# core_power.net
KiCad netlist of a schematic drawn in Altium Designer
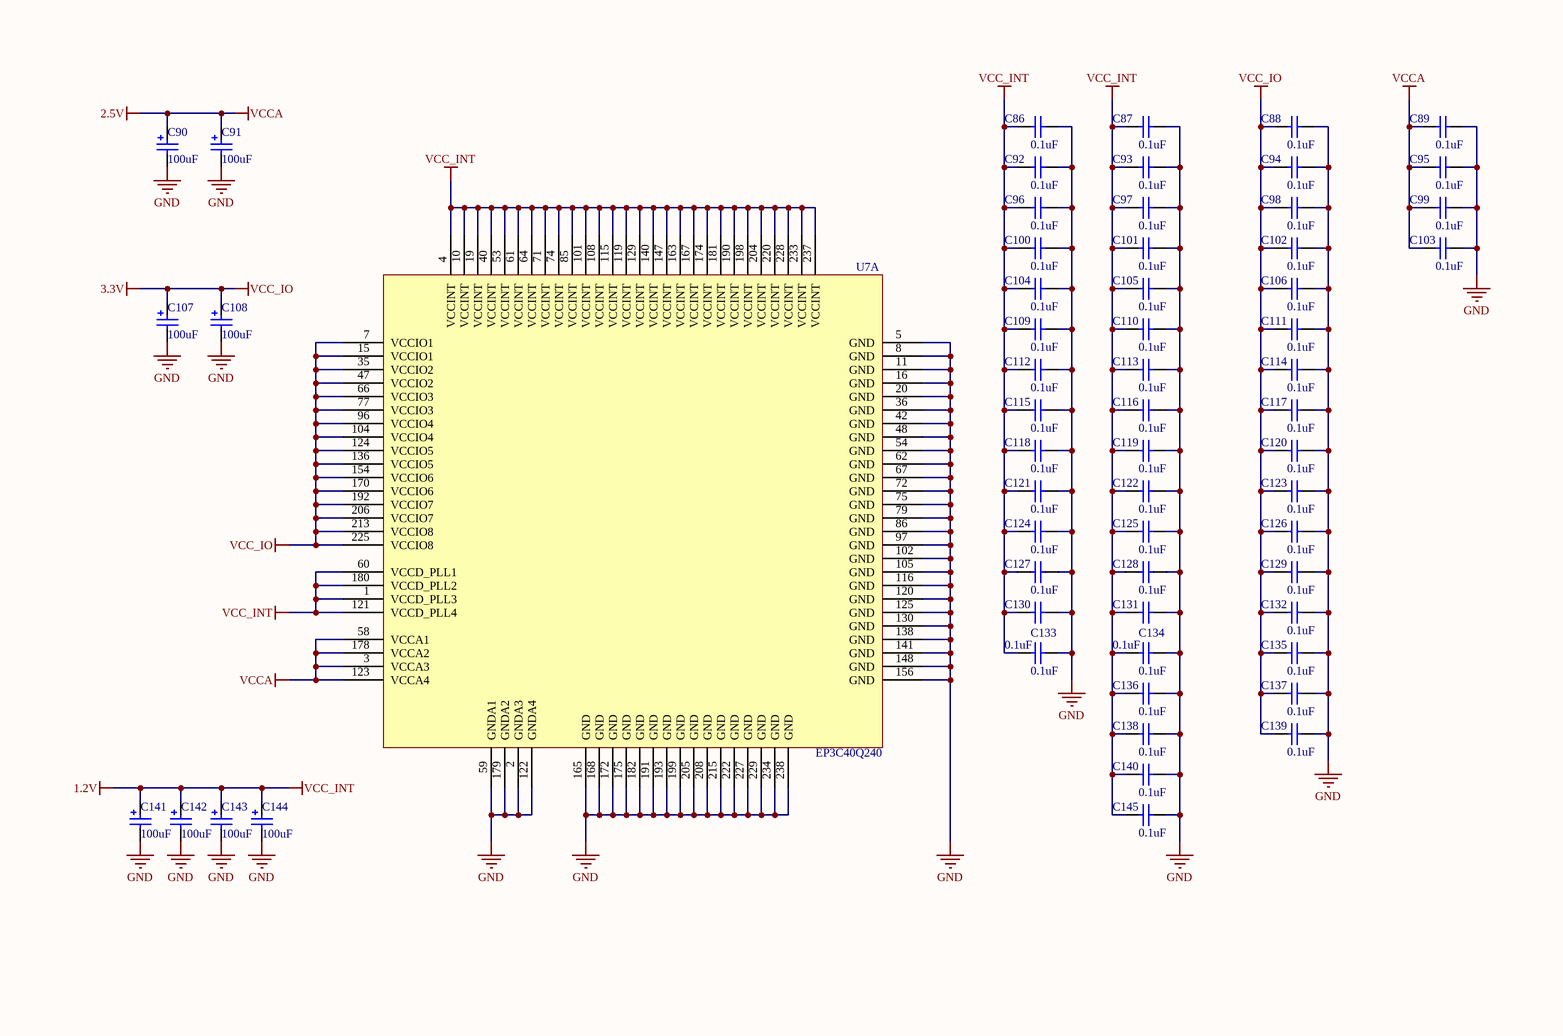
[diagram p0: core_power.SchDoc]

(export (version "E")
  (design (tool "Eeschema 10.0.6"))
  (components
    (comp (ref "C86")
      (value "0.1uF")
      (footprint "0402")
      (description "Capacitor")
      (fields (field (name "Comment") "Cap") (field (name "PUBLISHER") "Altium Limited"))
      (libsource (lib "Miscellaneous Devices") (part "Cap"))
    )
    (comp (ref "C87")
      (value "0.1uF")
      (footprint "0402")
      (description "Capacitor")
      (fields (field (name "Comment") "Cap") (field (name "PUBLISHER") "Altium Limited"))
      (libsource (lib "Miscellaneous Devices") (part "Cap"))
    )
    (comp (ref "C88")
      (value "0.1uF")
      (footprint "0402")
      (description "Capacitor")
      (fields (field (name "Comment") "Cap") (field (name "PUBLISHER") "Altium Limited"))
      (libsource (lib "Miscellaneous Devices") (part "Cap"))
    )
    (comp (ref "C89")
      (value "0.1uF")
      (footprint "0402")
      (description "Capacitor")
      (fields (field (name "Comment") "Cap") (field (name "PUBLISHER") "Altium Limited"))
      (libsource (lib "Miscellaneous Devices") (part "Cap"))
    )
    (comp (ref "C90")
      (value "100uF")
      (footprint "C1206_POLARIZED")
      (description "Polarized Capacitor (Axial)")
      (fields (field (name "Comment") "Cap") (field (name "PUBLISHER") "Altium Limited"))
      (libsource (lib "Miscellaneous Devices") (part "Cap Pol2"))
    )
    (comp (ref "C91")
      (value "100uF")
      (footprint "C1206_POLARIZED")
      (description "Polarized Capacitor (Axial)")
      (fields (field (name "Comment") "Cap") (field (name "PUBLISHER") "Altium Limited"))
      (libsource (lib "Miscellaneous Devices") (part "Cap Pol2"))
    )
    (comp (ref "C92")
      (value "0.1uF")
      (footprint "0402")
      (description "Capacitor")
      (fields (field (name "Comment") "Cap") (field (name "PUBLISHER") "Altium Limited"))
      (libsource (lib "Miscellaneous Devices") (part "Cap"))
    )
    (comp (ref "C93")
      (value "0.1uF")
      (footprint "0402")
      (description "Capacitor")
      (fields (field (name "Comment") "Cap") (field (name "PUBLISHER") "Altium Limited"))
      (libsource (lib "Miscellaneous Devices") (part "Cap"))
    )
    (comp (ref "C94")
      (value "0.1uF")
      (footprint "0402")
      (description "Capacitor")
      (fields (field (name "Comment") "Cap") (field (name "PUBLISHER") "Altium Limited"))
      (libsource (lib "Miscellaneous Devices") (part "Cap"))
    )
    (comp (ref "C95")
      (value "0.1uF")
      (footprint "0402")
      (description "Capacitor")
      (fields (field (name "Comment") "Cap") (field (name "PUBLISHER") "Altium Limited"))
      (libsource (lib "Miscellaneous Devices") (part "Cap"))
    )
    (comp (ref "C96")
      (value "0.1uF")
      (footprint "0402")
      (description "Capacitor")
      (fields (field (name "Comment") "Cap") (field (name "PUBLISHER") "Altium Limited"))
      (libsource (lib "Miscellaneous Devices") (part "Cap"))
    )
    (comp (ref "C97")
      (value "0.1uF")
      (footprint "0402")
      (description "Capacitor")
      (fields (field (name "Comment") "Cap") (field (name "PUBLISHER") "Altium Limited"))
      (libsource (lib "Miscellaneous Devices") (part "Cap"))
    )
    (comp (ref "C98")
      (value "0.1uF")
      (footprint "0402")
      (description "Capacitor")
      (fields (field (name "Comment") "Cap") (field (name "PUBLISHER") "Altium Limited"))
      (libsource (lib "Miscellaneous Devices") (part "Cap"))
    )
    (comp (ref "C99")
      (value "0.1uF")
      (footprint "0402")
      (description "Capacitor")
      (fields (field (name "Comment") "Cap") (field (name "PUBLISHER") "Altium Limited"))
      (libsource (lib "Miscellaneous Devices") (part "Cap"))
    )
    (comp (ref "C100")
      (value "0.1uF")
      (footprint "0402")
      (description "Capacitor")
      (fields (field (name "Comment") "Cap") (field (name "PUBLISHER") "Altium Limited"))
      (libsource (lib "Miscellaneous Devices") (part "Cap"))
    )
    (comp (ref "C101")
      (value "0.1uF")
      (footprint "0402")
      (description "Capacitor")
      (fields (field (name "Comment") "Cap") (field (name "PUBLISHER") "Altium Limited"))
      (libsource (lib "Miscellaneous Devices") (part "Cap"))
    )
    (comp (ref "C102")
      (value "0.1uF")
      (footprint "0402")
      (description "Capacitor")
      (fields (field (name "Comment") "Cap") (field (name "PUBLISHER") "Altium Limited"))
      (libsource (lib "Miscellaneous Devices") (part "Cap"))
    )
    (comp (ref "C103")
      (value "0.1uF")
      (footprint "0402")
      (description "Capacitor")
      (fields (field (name "Comment") "Cap") (field (name "PUBLISHER") "Altium Limited"))
      (libsource (lib "Miscellaneous Devices") (part "Cap"))
    )
    (comp (ref "C104")
      (value "0.1uF")
      (footprint "0402")
      (description "Capacitor")
      (fields (field (name "Comment") "Cap") (field (name "PUBLISHER") "Altium Limited"))
      (libsource (lib "Miscellaneous Devices") (part "Cap"))
    )
    (comp (ref "C105")
      (value "0.1uF")
      (footprint "0402")
      (description "Capacitor")
      (fields (field (name "Comment") "Cap") (field (name "PUBLISHER") "Altium Limited"))
      (libsource (lib "Miscellaneous Devices") (part "Cap"))
    )
    (comp (ref "C106")
      (value "0.1uF")
      (footprint "0402")
      (description "Capacitor")
      (fields (field (name "Comment") "Cap") (field (name "PUBLISHER") "Altium Limited"))
      (libsource (lib "Miscellaneous Devices") (part "Cap"))
    )
    (comp (ref "C107")
      (value "100uF")
      (footprint "C1206_POLARIZED")
      (description "Polarized Capacitor (Axial)")
      (fields (field (name "Comment") "Cap") (field (name "PUBLISHER") "Altium Limited"))
      (libsource (lib "Miscellaneous Devices") (part "Cap Pol2"))
    )
    (comp (ref "C108")
      (value "100uF")
      (footprint "C1206_POLARIZED")
      (description "Polarized Capacitor (Axial)")
      (fields (field (name "Comment") "Cap") (field (name "PUBLISHER") "Altium Limited"))
      (libsource (lib "Miscellaneous Devices") (part "Cap Pol2"))
    )
    (comp (ref "C109")
      (value "0.1uF")
      (footprint "0402")
      (description "Capacitor")
      (fields (field (name "Comment") "Cap") (field (name "PUBLISHER") "Altium Limited"))
      (libsource (lib "Miscellaneous Devices") (part "Cap"))
    )
    (comp (ref "C110")
      (value "0.1uF")
      (footprint "0402")
      (description "Capacitor")
      (fields (field (name "Comment") "Cap") (field (name "PUBLISHER") "Altium Limited"))
      (libsource (lib "Miscellaneous Devices") (part "Cap"))
    )
    (comp (ref "C111")
      (value "0.1uF")
      (footprint "0402")
      (description "Capacitor")
      (fields (field (name "Comment") "Cap") (field (name "PUBLISHER") "Altium Limited"))
      (libsource (lib "Miscellaneous Devices") (part "Cap"))
    )
    (comp (ref "C112")
      (value "0.1uF")
      (footprint "0402")
      (description "Capacitor")
      (fields (field (name "Comment") "Cap") (field (name "PUBLISHER") "Altium Limited"))
      (libsource (lib "Miscellaneous Devices") (part "Cap"))
    )
    (comp (ref "C113")
      (value "0.1uF")
      (footprint "0402")
      (description "Capacitor")
      (fields (field (name "Comment") "Cap") (field (name "PUBLISHER") "Altium Limited"))
      (libsource (lib "Miscellaneous Devices") (part "Cap"))
    )
    (comp (ref "C114")
      (value "0.1uF")
      (footprint "0402")
      (description "Capacitor")
      (fields (field (name "Comment") "Cap") (field (name "PUBLISHER") "Altium Limited"))
      (libsource (lib "Miscellaneous Devices") (part "Cap"))
    )
    (comp (ref "C115")
      (value "0.1uF")
      (footprint "0402")
      (description "Capacitor")
      (fields (field (name "Comment") "Cap") (field (name "PUBLISHER") "Altium Limited"))
      (libsource (lib "Miscellaneous Devices") (part "Cap"))
    )
    (comp (ref "C116")
      (value "0.1uF")
      (footprint "0402")
      (description "Capacitor")
      (fields (field (name "Comment") "Cap") (field (name "PUBLISHER") "Altium Limited"))
      (libsource (lib "Miscellaneous Devices") (part "Cap"))
    )
    (comp (ref "C117")
      (value "0.1uF")
      (footprint "0402")
      (description "Capacitor")
      (fields (field (name "Comment") "Cap") (field (name "PUBLISHER") "Altium Limited"))
      (libsource (lib "Miscellaneous Devices") (part "Cap"))
    )
    (comp (ref "C118")
      (value "0.1uF")
      (footprint "0402")
      (description "Capacitor")
      (fields (field (name "Comment") "Cap") (field (name "PUBLISHER") "Altium Limited"))
      (libsource (lib "Miscellaneous Devices") (part "Cap"))
    )
    (comp (ref "C119")
      (value "0.1uF")
      (footprint "0402")
      (description "Capacitor")
      (fields (field (name "Comment") "Cap") (field (name "PUBLISHER") "Altium Limited"))
      (libsource (lib "Miscellaneous Devices") (part "Cap"))
    )
    (comp (ref "C120")
      (value "0.1uF")
      (footprint "0402")
      (description "Capacitor")
      (fields (field (name "Comment") "Cap") (field (name "PUBLISHER") "Altium Limited"))
      (libsource (lib "Miscellaneous Devices") (part "Cap"))
    )
    (comp (ref "C121")
      (value "0.1uF")
      (footprint "0402")
      (description "Capacitor")
      (fields (field (name "Comment") "Cap") (field (name "PUBLISHER") "Altium Limited"))
      (libsource (lib "Miscellaneous Devices") (part "Cap"))
    )
    (comp (ref "C122")
      (value "0.1uF")
      (footprint "0402")
      (description "Capacitor")
      (fields (field (name "Comment") "Cap") (field (name "PUBLISHER") "Altium Limited"))
      (libsource (lib "Miscellaneous Devices") (part "Cap"))
    )
    (comp (ref "C123")
      (value "0.1uF")
      (footprint "0402")
      (description "Capacitor")
      (fields (field (name "Comment") "Cap") (field (name "PUBLISHER") "Altium Limited"))
      (libsource (lib "Miscellaneous Devices") (part "Cap"))
    )
    (comp (ref "C124")
      (value "0.1uF")
      (footprint "0402")
      (description "Capacitor")
      (fields (field (name "Comment") "Cap") (field (name "PUBLISHER") "Altium Limited"))
      (libsource (lib "Miscellaneous Devices") (part "Cap"))
    )
    (comp (ref "C125")
      (value "0.1uF")
      (footprint "0402")
      (description "Capacitor")
      (fields (field (name "Comment") "Cap") (field (name "PUBLISHER") "Altium Limited"))
      (libsource (lib "Miscellaneous Devices") (part "Cap"))
    )
    (comp (ref "C126")
      (value "0.1uF")
      (footprint "0402")
      (description "Capacitor")
      (fields (field (name "Comment") "Cap") (field (name "PUBLISHER") "Altium Limited"))
      (libsource (lib "Miscellaneous Devices") (part "Cap"))
    )
    (comp (ref "C127")
      (value "0.1uF")
      (footprint "0402")
      (description "Capacitor")
      (fields (field (name "Comment") "Cap") (field (name "PUBLISHER") "Altium Limited"))
      (libsource (lib "Miscellaneous Devices") (part "Cap"))
    )
    (comp (ref "C128")
      (value "0.1uF")
      (footprint "0402")
      (description "Capacitor")
      (fields (field (name "Comment") "Cap") (field (name "PUBLISHER") "Altium Limited"))
      (libsource (lib "Miscellaneous Devices") (part "Cap"))
    )
    (comp (ref "C129")
      (value "0.1uF")
      (footprint "0402")
      (description "Capacitor")
      (fields (field (name "Comment") "Cap") (field (name "PUBLISHER") "Altium Limited"))
      (libsource (lib "Miscellaneous Devices") (part "Cap"))
    )
    (comp (ref "C130")
      (value "0.1uF")
      (footprint "0402")
      (description "Capacitor")
      (fields (field (name "Comment") "Cap") (field (name "PUBLISHER") "Altium Limited"))
      (libsource (lib "Miscellaneous Devices") (part "Cap"))
    )
    (comp (ref "C131")
      (value "0.1uF")
      (footprint "0402")
      (description "Capacitor")
      (fields (field (name "Comment") "Cap") (field (name "PUBLISHER") "Altium Limited"))
      (libsource (lib "Miscellaneous Devices") (part "Cap"))
    )
    (comp (ref "C132")
      (value "0.1uF")
      (footprint "0402")
      (description "Capacitor")
      (fields (field (name "Comment") "Cap") (field (name "PUBLISHER") "Altium Limited"))
      (libsource (lib "Miscellaneous Devices") (part "Cap"))
    )
    (comp (ref "C133")
      (value "0.1uF")
      (footprint "0402")
      (description "Capacitor")
      (fields (field (name "Comment") "Cap") (field (name "PUBLISHER") "Altium Limited"))
      (libsource (lib "Miscellaneous Devices") (part "Cap"))
    )
    (comp (ref "C134")
      (value "0.1uF")
      (footprint "0402")
      (description "Capacitor")
      (fields (field (name "Comment") "Cap") (field (name "PUBLISHER") "Altium Limited"))
      (libsource (lib "Miscellaneous Devices") (part "Cap"))
    )
    (comp (ref "C135")
      (value "0.1uF")
      (footprint "0402")
      (description "Capacitor")
      (fields (field (name "Comment") "Cap") (field (name "PUBLISHER") "Altium Limited"))
      (libsource (lib "Miscellaneous Devices") (part "Cap"))
    )
    (comp (ref "C136")
      (value "0.1uF")
      (footprint "0402")
      (description "Capacitor")
      (fields (field (name "Comment") "Cap") (field (name "PUBLISHER") "Altium Limited"))
      (libsource (lib "Miscellaneous Devices") (part "Cap"))
    )
    (comp (ref "C137")
      (value "0.1uF")
      (footprint "0402")
      (description "Capacitor")
      (fields (field (name "Comment") "Cap") (field (name "PUBLISHER") "Altium Limited"))
      (libsource (lib "Miscellaneous Devices") (part "Cap"))
    )
    (comp (ref "C138")
      (value "0.1uF")
      (footprint "0402")
      (description "Capacitor")
      (fields (field (name "Comment") "Cap") (field (name "PUBLISHER") "Altium Limited"))
      (libsource (lib "Miscellaneous Devices") (part "Cap"))
    )
    (comp (ref "C139")
      (value "0.1uF")
      (footprint "0402")
      (description "Capacitor")
      (fields (field (name "Comment") "Cap") (field (name "PUBLISHER") "Altium Limited"))
      (libsource (lib "Miscellaneous Devices") (part "Cap"))
    )
    (comp (ref "C140")
      (value "0.1uF")
      (footprint "0402")
      (description "Capacitor")
      (fields (field (name "Comment") "Cap") (field (name "PUBLISHER") "Altium Limited"))
      (libsource (lib "Miscellaneous Devices") (part "Cap"))
    )
    (comp (ref "C141")
      (value "100uF")
      (footprint "C1206_POLARIZED")
      (description "Polarized Capacitor (Axial)")
      (fields (field (name "Comment") "Cap Pol2") (field (name "PUBLISHER") "Altium Limited"))
      (libsource (lib "Miscellaneous Devices") (part "Cap Pol2"))
    )
    (comp (ref "C142")
      (value "100uF")
      (footprint "C1206_POLARIZED")
      (description "Polarized Capacitor (Axial)")
      (fields (field (name "Comment") "Cap Pol2") (field (name "PUBLISHER") "Altium Limited"))
      (libsource (lib "Miscellaneous Devices") (part "Cap Pol2"))
    )
    (comp (ref "C143")
      (value "100uF")
      (footprint "C1206_POLARIZED")
      (description "Polarized Capacitor (Axial)")
      (fields (field (name "Comment") "Cap") (field (name "PUBLISHER") "Altium Limited"))
      (libsource (lib "Miscellaneous Devices") (part "Cap Pol2"))
    )
    (comp (ref "C144")
      (value "100uF")
      (footprint "C1206_POLARIZED")
      (description "Polarized Capacitor (Axial)")
      (fields (field (name "Comment") "Cap") (field (name "PUBLISHER") "Altium Limited"))
      (libsource (lib "Miscellaneous Devices") (part "Cap Pol2"))
    )
    (comp (ref "C145")
      (value "0.1uF")
      (footprint "0402")
      (description "Capacitor")
      (fields (field (name "Comment") "Cap") (field (name "PUBLISHER") "Altium Limited"))
      (libsource (lib "Miscellaneous Devices") (part "Cap"))
    )
    (comp (ref "U7")
      (value "EP3C40Q240")
      (footprint "PQFP240")
      (libsource (lib "FPGA_board") (part "EP3C40Q240"))
    )
  )
  (nets
    (net (code "1") (name "1.2V") (class "Default")
      (node (ref "C100") (pin "1") (pinfunction "1_1") (pintype "passive"))
      (node (ref "C101") (pin "1") (pinfunction "1_1") (pintype "passive"))
      (node (ref "C104") (pin "1") (pinfunction "1_1") (pintype "passive"))
      (node (ref "C105") (pin "1") (pinfunction "1_1") (pintype "passive"))
      (node (ref "C109") (pin "1") (pinfunction "1_1") (pintype "passive"))
      (node (ref "C110") (pin "1") (pinfunction "1_1") (pintype "passive"))
      (node (ref "C112") (pin "1") (pinfunction "1_1") (pintype "passive"))
      (node (ref "C113") (pin "1") (pinfunction "1_1") (pintype "passive"))
      (node (ref "C115") (pin "1") (pinfunction "1_1") (pintype "passive"))
      (node (ref "C116") (pin "1") (pinfunction "1_1") (pintype "passive"))
      (node (ref "C118") (pin "1") (pinfunction "1_1") (pintype "passive"))
      (node (ref "C119") (pin "1") (pinfunction "1_1") (pintype "passive"))
      (node (ref "C121") (pin "1") (pinfunction "1_1") (pintype "passive"))
      (node (ref "C122") (pin "1") (pinfunction "1_1") (pintype "passive"))
      (node (ref "C124") (pin "1") (pinfunction "1_1") (pintype "passive"))
      (node (ref "C125") (pin "1") (pinfunction "1_1") (pintype "passive"))
      (node (ref "C127") (pin "1") (pinfunction "1_1") (pintype "passive"))
      (node (ref "C128") (pin "1") (pinfunction "1_1") (pintype "passive"))
      (node (ref "C130") (pin "1") (pinfunction "1_1") (pintype "passive"))
      (node (ref "C131") (pin "1") (pinfunction "1_1") (pintype "passive"))
      (node (ref "C133") (pin "1") (pinfunction "1_1") (pintype "passive"))
      (node (ref "C134") (pin "1") (pinfunction "1_1") (pintype "passive"))
      (node (ref "C136") (pin "1") (pinfunction "1_1") (pintype "passive"))
      (node (ref "C138") (pin "1") (pinfunction "1_1") (pintype "passive"))
      (node (ref "C140") (pin "1") (pinfunction "1_1") (pintype "passive"))
      (node (ref "C141") (pin "1") (pinfunction "1_1") (pintype "passive"))
      (node (ref "C142") (pin "1") (pinfunction "1_1") (pintype "passive"))
      (node (ref "C143") (pin "1") (pinfunction "1_1") (pintype "passive"))
      (node (ref "C144") (pin "1") (pinfunction "1_1") (pintype "passive"))
      (node (ref "C145") (pin "1") (pinfunction "1_1") (pintype "passive"))
      (node (ref "C86") (pin "1") (pinfunction "1_1") (pintype "passive"))
      (node (ref "C87") (pin "1") (pinfunction "1_1") (pintype "passive"))
      (node (ref "C92") (pin "1") (pinfunction "1_1") (pintype "passive"))
      (node (ref "C93") (pin "1") (pinfunction "1_1") (pintype "passive"))
      (node (ref "C96") (pin "1") (pinfunction "1_1") (pintype "passive"))
      (node (ref "C97") (pin "1") (pinfunction "1_1") (pintype "passive"))
      (node (ref "U7") (pin "1") (pinfunction "VCCD_PLL3_1") (pintype "power_in"))
      (node (ref "U7") (pin "10") (pinfunction "VCCINT_10") (pintype "power_in"))
      (node (ref "U7") (pin "101") (pinfunction "VCCINT_101") (pintype "power_in"))
      (node (ref "U7") (pin "108") (pinfunction "VCCINT_108") (pintype "power_in"))
      (node (ref "U7") (pin "115") (pinfunction "VCCINT_115") (pintype "power_in"))
      (node (ref "U7") (pin "119") (pinfunction "VCCINT_119") (pintype "power_in"))
      (node (ref "U7") (pin "121") (pinfunction "VCCD_PLL4_121") (pintype "power_in"))
      (node (ref "U7") (pin "129") (pinfunction "VCCINT_129") (pintype "power_in"))
      (node (ref "U7") (pin "140") (pinfunction "VCCINT_140") (pintype "power_in"))
      (node (ref "U7") (pin "147") (pinfunction "VCCINT_147") (pintype "power_in"))
      (node (ref "U7") (pin "163") (pinfunction "VCCINT_163") (pintype "power_in"))
      (node (ref "U7") (pin "167") (pinfunction "VCCINT_167") (pintype "power_in"))
      (node (ref "U7") (pin "174") (pinfunction "VCCINT_174") (pintype "power_in"))
      (node (ref "U7") (pin "180") (pinfunction "VCCD_PLL2_180") (pintype "power_in"))
      (node (ref "U7") (pin "181") (pinfunction "VCCINT_181") (pintype "power_in"))
      (node (ref "U7") (pin "19") (pinfunction "VCCINT_19") (pintype "power_in"))
      (node (ref "U7") (pin "190") (pinfunction "VCCINT_190") (pintype "power_in"))
      (node (ref "U7") (pin "198") (pinfunction "VCCINT_198") (pintype "power_in"))
      (node (ref "U7") (pin "204") (pinfunction "VCCINT_204") (pintype "power_in"))
      (node (ref "U7") (pin "220") (pinfunction "VCCINT_220") (pintype "power_in"))
      (node (ref "U7") (pin "228") (pinfunction "VCCINT_228") (pintype "power_in"))
      (node (ref "U7") (pin "233") (pinfunction "VCCINT_233") (pintype "power_in"))
      (node (ref "U7") (pin "237") (pinfunction "VCCINT_237") (pintype "power_in"))
      (node (ref "U7") (pin "4") (pinfunction "VCCINT_4") (pintype "power_in"))
      (node (ref "U7") (pin "40") (pinfunction "VCCINT_40") (pintype "power_in"))
      (node (ref "U7") (pin "53") (pinfunction "VCCINT_53") (pintype "power_in"))
      (node (ref "U7") (pin "60") (pinfunction "VCCD_PLL1_60") (pintype "power_in"))
      (node (ref "U7") (pin "61") (pinfunction "VCCINT_61") (pintype "power_in"))
      (node (ref "U7") (pin "64") (pinfunction "VCCINT_64") (pintype "power_in"))
      (node (ref "U7") (pin "71") (pinfunction "VCCINT_71") (pintype "power_in"))
      (node (ref "U7") (pin "74") (pinfunction "VCCINT_74") (pintype "power_in"))
      (node (ref "U7") (pin "85") (pinfunction "VCCINT_85") (pintype "power_in"))
    )
    (net (code "2") (name "2.5V") (class "Default")
      (node (ref "C103") (pin "1") (pinfunction "1_1") (pintype "passive"))
      (node (ref "C89") (pin "1") (pinfunction "1_1") (pintype "passive"))
      (node (ref "C90") (pin "1") (pinfunction "1_1") (pintype "passive"))
      (node (ref "C91") (pin "1") (pinfunction "1_1") (pintype "passive"))
      (node (ref "C95") (pin "1") (pinfunction "1_1") (pintype "passive"))
      (node (ref "C99") (pin "1") (pinfunction "1_1") (pintype "passive"))
      (node (ref "U7") (pin "123") (pinfunction "VCCA4_123") (pintype "power_in"))
      (node (ref "U7") (pin "178") (pinfunction "VCCA2_178") (pintype "power_in"))
      (node (ref "U7") (pin "3") (pinfunction "VCCA3_3") (pintype "power_in"))
      (node (ref "U7") (pin "58") (pinfunction "VCCA1_58") (pintype "power_in"))
    )
    (net (code "3") (name "3.3V") (class "Default")
      (node (ref "C102") (pin "1") (pinfunction "1_1") (pintype "passive"))
      (node (ref "C106") (pin "1") (pinfunction "1_1") (pintype "passive"))
      (node (ref "C107") (pin "1") (pinfunction "1_1") (pintype "passive"))
      (node (ref "C108") (pin "1") (pinfunction "1_1") (pintype "passive"))
      (node (ref "C111") (pin "1") (pinfunction "1_1") (pintype "passive"))
      (node (ref "C114") (pin "1") (pinfunction "1_1") (pintype "passive"))
      (node (ref "C117") (pin "1") (pinfunction "1_1") (pintype "passive"))
      (node (ref "C120") (pin "1") (pinfunction "1_1") (pintype "passive"))
      (node (ref "C123") (pin "1") (pinfunction "1_1") (pintype "passive"))
      (node (ref "C126") (pin "1") (pinfunction "1_1") (pintype "passive"))
      (node (ref "C129") (pin "1") (pinfunction "1_1") (pintype "passive"))
      (node (ref "C132") (pin "1") (pinfunction "1_1") (pintype "passive"))
      (node (ref "C135") (pin "1") (pinfunction "1_1") (pintype "passive"))
      (node (ref "C137") (pin "1") (pinfunction "1_1") (pintype "passive"))
      (node (ref "C139") (pin "1") (pinfunction "1_1") (pintype "passive"))
      (node (ref "C88") (pin "1") (pinfunction "1_1") (pintype "passive"))
      (node (ref "C94") (pin "1") (pinfunction "1_1") (pintype "passive"))
      (node (ref "C98") (pin "1") (pinfunction "1_1") (pintype "passive"))
      (node (ref "U7") (pin "104") (pinfunction "VCCIO4_104") (pintype "power_in"))
      (node (ref "U7") (pin "124") (pinfunction "VCCIO5_124") (pintype "power_in"))
      (node (ref "U7") (pin "136") (pinfunction "VCCIO5_136") (pintype "power_in"))
      (node (ref "U7") (pin "15") (pinfunction "VCCIO1_15") (pintype "power_in"))
      (node (ref "U7") (pin "154") (pinfunction "VCCIO6_154") (pintype "power_in"))
      (node (ref "U7") (pin "170") (pinfunction "VCCIO6_170") (pintype "power_in"))
      (node (ref "U7") (pin "192") (pinfunction "VCCIO7_192") (pintype "power_in"))
      (node (ref "U7") (pin "206") (pinfunction "VCCIO7_206") (pintype "power_in"))
      (node (ref "U7") (pin "213") (pinfunction "VCCIO8_213") (pintype "power_in"))
      (node (ref "U7") (pin "225") (pinfunction "VCCIO8_225") (pintype "power_in"))
      (node (ref "U7") (pin "35") (pinfunction "VCCIO2_35") (pintype "power_in"))
      (node (ref "U7") (pin "47") (pinfunction "VCCIO2_47") (pintype "power_in"))
      (node (ref "U7") (pin "66") (pinfunction "VCCIO3_66") (pintype "power_in"))
      (node (ref "U7") (pin "7") (pinfunction "VCCIO1_7") (pintype "power_in"))
      (node (ref "U7") (pin "77") (pinfunction "VCCIO3_77") (pintype "power_in"))
      (node (ref "U7") (pin "96") (pinfunction "VCCIO4_96") (pintype "power_in"))
    )
    (net (code "4") (name "GND") (class "Default")
      (node (ref "C100") (pin "2") (pinfunction "2_2") (pintype "passive"))
      (node (ref "C101") (pin "2") (pinfunction "2_2") (pintype "passive"))
      (node (ref "C102") (pin "2") (pinfunction "2_2") (pintype "passive"))
      (node (ref "C103") (pin "2") (pinfunction "2_2") (pintype "passive"))
      (node (ref "C104") (pin "2") (pinfunction "2_2") (pintype "passive"))
      (node (ref "C105") (pin "2") (pinfunction "2_2") (pintype "passive"))
      (node (ref "C106") (pin "2") (pinfunction "2_2") (pintype "passive"))
      (node (ref "C107") (pin "2") (pinfunction "2_2") (pintype "passive"))
      (node (ref "C108") (pin "2") (pinfunction "2_2") (pintype "passive"))
      (node (ref "C109") (pin "2") (pinfunction "2_2") (pintype "passive"))
      (node (ref "C110") (pin "2") (pinfunction "2_2") (pintype "passive"))
      (node (ref "C111") (pin "2") (pinfunction "2_2") (pintype "passive"))
      (node (ref "C112") (pin "2") (pinfunction "2_2") (pintype "passive"))
      (node (ref "C113") (pin "2") (pinfunction "2_2") (pintype "passive"))
      (node (ref "C114") (pin "2") (pinfunction "2_2") (pintype "passive"))
      (node (ref "C115") (pin "2") (pinfunction "2_2") (pintype "passive"))
      (node (ref "C116") (pin "2") (pinfunction "2_2") (pintype "passive"))
      (node (ref "C117") (pin "2") (pinfunction "2_2") (pintype "passive"))
      (node (ref "C118") (pin "2") (pinfunction "2_2") (pintype "passive"))
      (node (ref "C119") (pin "2") (pinfunction "2_2") (pintype "passive"))
      (node (ref "C120") (pin "2") (pinfunction "2_2") (pintype "passive"))
      (node (ref "C121") (pin "2") (pinfunction "2_2") (pintype "passive"))
      (node (ref "C122") (pin "2") (pinfunction "2_2") (pintype "passive"))
      (node (ref "C123") (pin "2") (pinfunction "2_2") (pintype "passive"))
      (node (ref "C124") (pin "2") (pinfunction "2_2") (pintype "passive"))
      (node (ref "C125") (pin "2") (pinfunction "2_2") (pintype "passive"))
      (node (ref "C126") (pin "2") (pinfunction "2_2") (pintype "passive"))
      (node (ref "C127") (pin "2") (pinfunction "2_2") (pintype "passive"))
      (node (ref "C128") (pin "2") (pinfunction "2_2") (pintype "passive"))
      (node (ref "C129") (pin "2") (pinfunction "2_2") (pintype "passive"))
      (node (ref "C130") (pin "2") (pinfunction "2_2") (pintype "passive"))
      (node (ref "C131") (pin "2") (pinfunction "2_2") (pintype "passive"))
      (node (ref "C132") (pin "2") (pinfunction "2_2") (pintype "passive"))
      (node (ref "C133") (pin "2") (pinfunction "2_2") (pintype "passive"))
      (node (ref "C134") (pin "2") (pinfunction "2_2") (pintype "passive"))
      (node (ref "C135") (pin "2") (pinfunction "2_2") (pintype "passive"))
      (node (ref "C136") (pin "2") (pinfunction "2_2") (pintype "passive"))
      (node (ref "C137") (pin "2") (pinfunction "2_2") (pintype "passive"))
      (node (ref "C138") (pin "2") (pinfunction "2_2") (pintype "passive"))
      (node (ref "C139") (pin "2") (pinfunction "2_2") (pintype "passive"))
      (node (ref "C140") (pin "2") (pinfunction "2_2") (pintype "passive"))
      (node (ref "C141") (pin "2") (pinfunction "2_2") (pintype "passive"))
      (node (ref "C142") (pin "2") (pinfunction "2_2") (pintype "passive"))
      (node (ref "C143") (pin "2") (pinfunction "2_2") (pintype "passive"))
      (node (ref "C144") (pin "2") (pinfunction "2_2") (pintype "passive"))
      (node (ref "C145") (pin "2") (pinfunction "2_2") (pintype "passive"))
      (node (ref "C86") (pin "2") (pinfunction "2_2") (pintype "passive"))
      (node (ref "C87") (pin "2") (pinfunction "2_2") (pintype "passive"))
      (node (ref "C88") (pin "2") (pinfunction "2_2") (pintype "passive"))
      (node (ref "C89") (pin "2") (pinfunction "2_2") (pintype "passive"))
      (node (ref "C90") (pin "2") (pinfunction "2_2") (pintype "passive"))
      (node (ref "C91") (pin "2") (pinfunction "2_2") (pintype "passive"))
      (node (ref "C92") (pin "2") (pinfunction "2_2") (pintype "passive"))
      (node (ref "C93") (pin "2") (pinfunction "2_2") (pintype "passive"))
      (node (ref "C94") (pin "2") (pinfunction "2_2") (pintype "passive"))
      (node (ref "C95") (pin "2") (pinfunction "2_2") (pintype "passive"))
      (node (ref "C96") (pin "2") (pinfunction "2_2") (pintype "passive"))
      (node (ref "C97") (pin "2") (pinfunction "2_2") (pintype "passive"))
      (node (ref "C98") (pin "2") (pinfunction "2_2") (pintype "passive"))
      (node (ref "C99") (pin "2") (pinfunction "2_2") (pintype "passive"))
      (node (ref "U7") (pin "102") (pinfunction "GND_102") (pintype "power_in"))
      (node (ref "U7") (pin "105") (pinfunction "GND_105") (pintype "power_in"))
      (node (ref "U7") (pin "11") (pinfunction "GND_11") (pintype "power_in"))
      (node (ref "U7") (pin "116") (pinfunction "GND_116") (pintype "power_in"))
      (node (ref "U7") (pin "120") (pinfunction "GND_120") (pintype "power_in"))
      (node (ref "U7") (pin "122") (pinfunction "GNDA4_122") (pintype "power_in"))
      (node (ref "U7") (pin "125") (pinfunction "GND_125") (pintype "power_in"))
      (node (ref "U7") (pin "130") (pinfunction "GND_130") (pintype "power_in"))
      (node (ref "U7") (pin "138") (pinfunction "GND_138") (pintype "power_in"))
      (node (ref "U7") (pin "141") (pinfunction "GND_141") (pintype "power_in"))
      (node (ref "U7") (pin "148") (pinfunction "GND_148") (pintype "power_in"))
      (node (ref "U7") (pin "156") (pinfunction "GND_156") (pintype "power_in"))
      (node (ref "U7") (pin "16") (pinfunction "GND_16") (pintype "power_in"))
      (node (ref "U7") (pin "165") (pinfunction "GND_165") (pintype "power_in"))
      (node (ref "U7") (pin "168") (pinfunction "GND_168") (pintype "power_in"))
      (node (ref "U7") (pin "172") (pinfunction "GND_172") (pintype "power_in"))
      (node (ref "U7") (pin "175") (pinfunction "GND_175") (pintype "power_in"))
      (node (ref "U7") (pin "179") (pinfunction "GNDA2_179") (pintype "power_in"))
      (node (ref "U7") (pin "182") (pinfunction "GND_182") (pintype "power_in"))
      (node (ref "U7") (pin "191") (pinfunction "GND_191") (pintype "power_in"))
      (node (ref "U7") (pin "193") (pinfunction "GND_193") (pintype "power_in"))
      (node (ref "U7") (pin "199") (pinfunction "GND_199") (pintype "power_in"))
      (node (ref "U7") (pin "2") (pinfunction "GNDA3_2") (pintype "power_in"))
      (node (ref "U7") (pin "20") (pinfunction "GND_20") (pintype "power_in"))
      (node (ref "U7") (pin "205") (pinfunction "GND_205") (pintype "power_in"))
      (node (ref "U7") (pin "208") (pinfunction "GND_208") (pintype "power_in"))
      (node (ref "U7") (pin "215") (pinfunction "GND_215") (pintype "power_in"))
      (node (ref "U7") (pin "222") (pinfunction "GND_222") (pintype "power_in"))
      (node (ref "U7") (pin "227") (pinfunction "GND_227") (pintype "power_in"))
      (node (ref "U7") (pin "229") (pinfunction "GND_229") (pintype "power_in"))
      (node (ref "U7") (pin "234") (pinfunction "GND_234") (pintype "power_in"))
      (node (ref "U7") (pin "238") (pinfunction "GND_238") (pintype "power_in"))
      (node (ref "U7") (pin "36") (pinfunction "GND_36") (pintype "power_in"))
      (node (ref "U7") (pin "42") (pinfunction "GND_42") (pintype "power_in"))
      (node (ref "U7") (pin "48") (pinfunction "GND_48") (pintype "power_in"))
      (node (ref "U7") (pin "5") (pinfunction "GND_5") (pintype "power_in"))
      (node (ref "U7") (pin "54") (pinfunction "GND_54") (pintype "power_in"))
      (node (ref "U7") (pin "59") (pinfunction "GNDA1_59") (pintype "power_in"))
      (node (ref "U7") (pin "62") (pinfunction "GND_62") (pintype "power_in"))
      (node (ref "U7") (pin "67") (pinfunction "GND_67") (pintype "power_in"))
      (node (ref "U7") (pin "72") (pinfunction "GND_72") (pintype "power_in"))
      (node (ref "U7") (pin "75") (pinfunction "GND_75") (pintype "power_in"))
      (node (ref "U7") (pin "79") (pinfunction "GND_79") (pintype "power_in"))
      (node (ref "U7") (pin "8") (pinfunction "GND_8") (pintype "power_in"))
      (node (ref "U7") (pin "86") (pinfunction "GND_86") (pintype "power_in"))
      (node (ref "U7") (pin "97") (pinfunction "GND_97") (pintype "power_in"))
    )
  )
)
